# eib-64-large.net
KiCad netlist of a schematic drawn in EAGLE
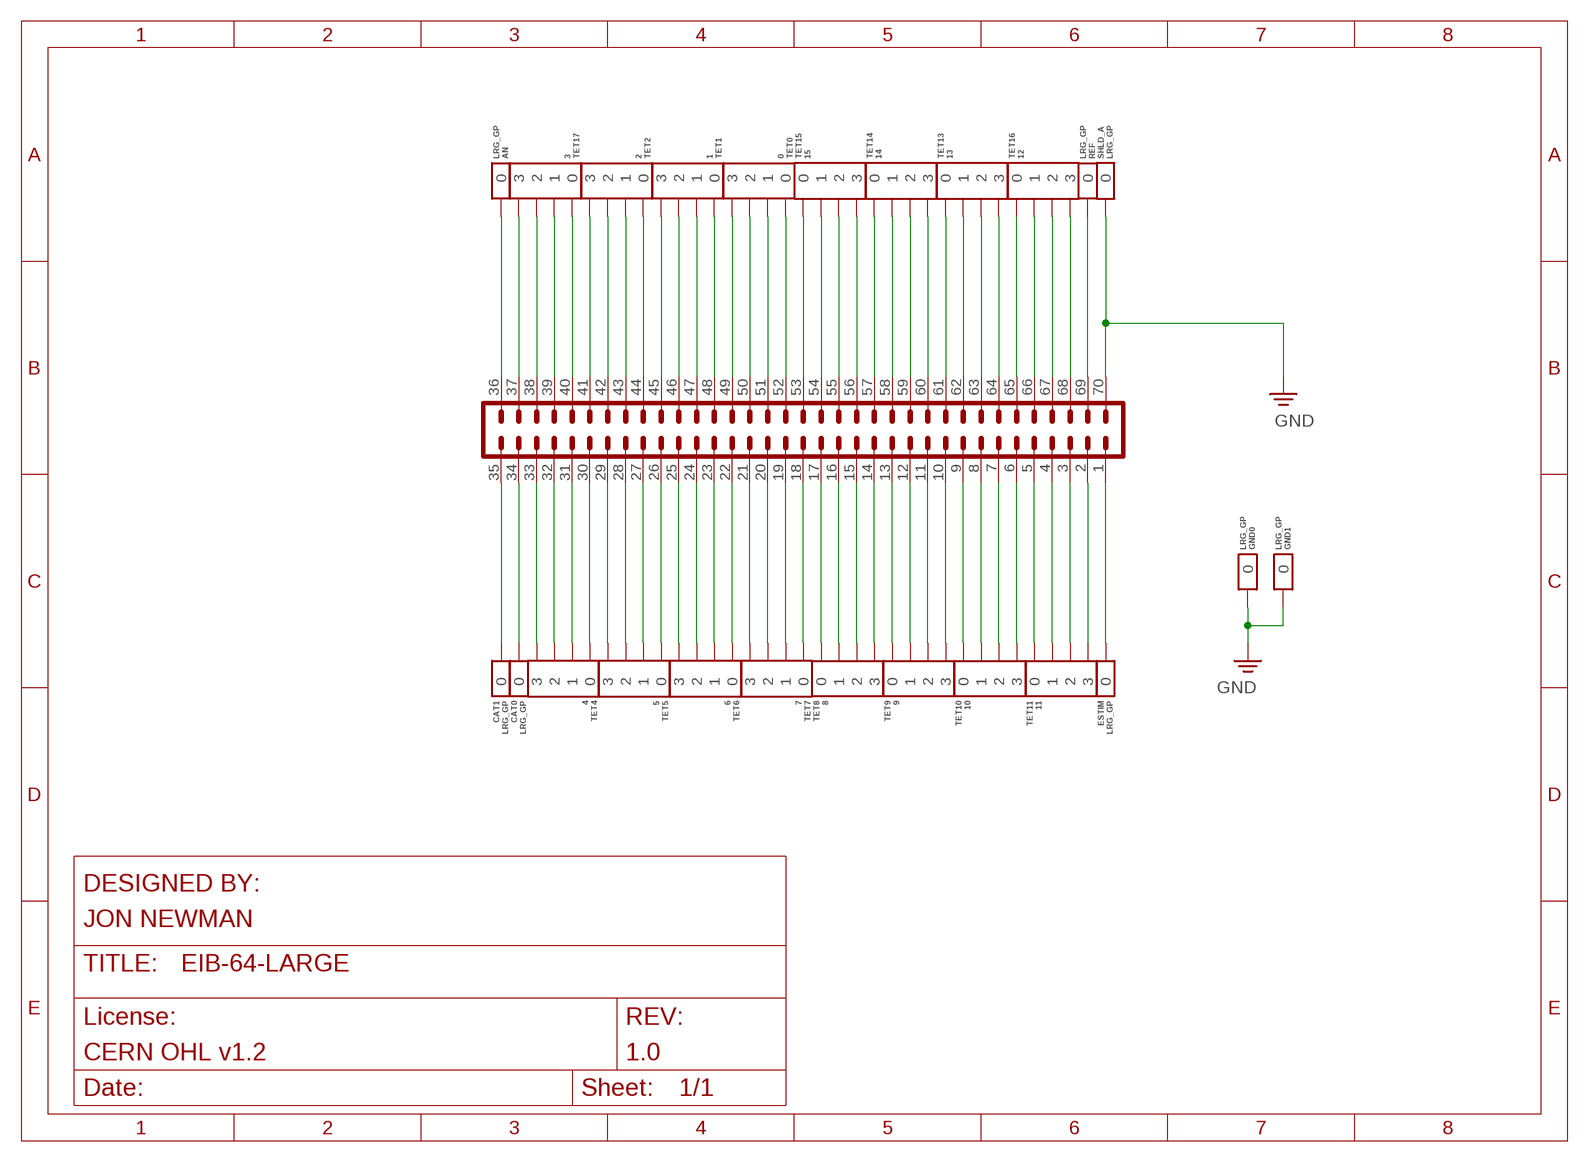
[diagram p0: schematic, sheet 1]

(export (version "E")
  (design (tool "Eeschema 10.0.6"))
  (components
    (comp (ref "AN")
      (value "LRG_GP")
      (footprint "eagle-import:GOLDPIN_0.5ID_0.7OD")
      (libsource (lib "eagle-import") (part "GOLDPIN_0.5ID_0.7OD"))
    )
    (comp (ref "CAT0")
      (value "LRG_GP")
      (footprint "eagle-import:GOLDPIN_0.5ID_0.7OD")
      (libsource (lib "eagle-import") (part "GOLDPIN_0.5ID_0.7OD"))
    )
    (comp (ref "CAT1")
      (value "LRG_GP")
      (footprint "eagle-import:GOLDPIN_0.5ID_0.7OD")
      (libsource (lib "eagle-import") (part "GOLDPIN_0.5ID_0.7OD"))
    )
    (comp (ref "ESTIM")
      (value "LRG_GP")
      (footprint "eagle-import:GOLDPIN_0.5ID_0.7OD")
      (libsource (lib "eagle-import") (part "GOLDPIN_0.5ID_0.7OD"))
    )
    (comp (ref "GND0")
      (value "LRG_GP")
      (footprint "eagle-import:GOLDPIN_0.5ID_0.7OD")
      (libsource (lib "eagle-import") (part "GOLDPIN_0.5ID_0.7OD"))
    )
    (comp (ref "GND1")
      (value "LRG_GP")
      (footprint "eagle-import:GOLDPIN_0.5ID_0.7OD")
      (libsource (lib "eagle-import") (part "GOLDPIN_0.5ID_0.7OD"))
    )
    (comp (ref "J1")
      (value "DF40-REC")
      (footprint "eagle-import:DDF40-70REC-LRG")
      (libsource (lib "eagle-import") (part "PINHD-2X35_DF40REF-LRG"))
    )
    (comp (ref "REF")
      (value "LRG_GP")
      (footprint "eagle-import:GOLDPIN_0.5ID_0.7OD")
      (libsource (lib "eagle-import") (part "GOLDPIN_0.5ID_0.7OD"))
    )
    (comp (ref "SHLD_A")
      (value "LRG_GP")
      (footprint "eagle-import:GOLDPIN_0.5ID_0.7OD")
      (libsource (lib "eagle-import") (part "GOLDPIN_0.5ID_0.7OD"))
    )
    (comp (ref "TET0")
      (value "0")
      (footprint "eagle-import:TETRODE_128_0.5ID_0.7OD")
      (libsource (lib "eagle-import") (part "TETRODE_128_0.5ID_0.7OD"))
    )
    (comp (ref "TET1")
      (value "1")
      (footprint "eagle-import:TETRODE_128_0.5ID_0.7OD")
      (libsource (lib "eagle-import") (part "TETRODE_128_0.5ID_0.7OD"))
    )
    (comp (ref "TET2")
      (value "2")
      (footprint "eagle-import:TETRODE_128_0.5ID_0.7OD")
      (libsource (lib "eagle-import") (part "TETRODE_128_0.5ID_0.7OD"))
    )
    (comp (ref "TET4")
      (value "4")
      (footprint "eagle-import:TETRODE_128_0.5ID_0.7OD")
      (libsource (lib "eagle-import") (part "TETRODE_128_0.5ID_0.7OD"))
    )
    (comp (ref "TET5")
      (value "5")
      (footprint "eagle-import:TETRODE_128_0.5ID_0.7OD")
      (libsource (lib "eagle-import") (part "TETRODE_128_0.5ID_0.7OD"))
    )
    (comp (ref "TET6")
      (value "6")
      (footprint "eagle-import:TETRODE_128_0.5ID_0.7OD")
      (libsource (lib "eagle-import") (part "TETRODE_128_0.5ID_0.7OD"))
    )
    (comp (ref "TET7")
      (value "7")
      (footprint "eagle-import:TETRODE_128_0.5ID_0.7OD")
      (libsource (lib "eagle-import") (part "TETRODE_128_0.5ID_0.7OD"))
    )
    (comp (ref "TET8")
      (value "8")
      (footprint "eagle-import:TETRODE_128_0.5ID_0.7OD")
      (libsource (lib "eagle-import") (part "TETRODE_128_0.5ID_0.7OD"))
    )
    (comp (ref "TET9")
      (value "9")
      (footprint "eagle-import:TETRODE_128_0.5ID_0.7OD")
      (libsource (lib "eagle-import") (part "TETRODE_128_0.5ID_0.7OD"))
    )
    (comp (ref "TET10")
      (value "10")
      (footprint "eagle-import:TETRODE_128_0.5ID_0.7OD")
      (libsource (lib "eagle-import") (part "TETRODE_128_0.5ID_0.7OD"))
    )
    (comp (ref "TET11")
      (value "11")
      (footprint "eagle-import:TETRODE_128_0.5ID_0.7OD")
      (libsource (lib "eagle-import") (part "TETRODE_128_0.5ID_0.7OD"))
    )
    (comp (ref "TET13")
      (value "13")
      (footprint "eagle-import:TETRODE_128_0.5ID_0.7OD")
      (libsource (lib "eagle-import") (part "TETRODE_128_0.5ID_0.7OD"))
    )
    (comp (ref "TET14")
      (value "14")
      (footprint "eagle-import:TETRODE_128_0.5ID_0.7OD")
      (libsource (lib "eagle-import") (part "TETRODE_128_0.5ID_0.7OD"))
    )
    (comp (ref "TET15")
      (value "15")
      (footprint "eagle-import:TETRODE_128_0.5ID_0.7OD")
      (libsource (lib "eagle-import") (part "TETRODE_128_0.5ID_0.7OD"))
    )
    (comp (ref "TET16")
      (value "12")
      (footprint "eagle-import:TETRODE_128_0.5ID_0.7OD")
      (libsource (lib "eagle-import") (part "TETRODE_128_0.5ID_0.7OD"))
    )
    (comp (ref "TET17")
      (value "3")
      (footprint "eagle-import:TETRODE_128_0.5ID_0.7OD")
      (libsource (lib "eagle-import") (part "TETRODE_128_0.5ID_0.7OD"))
    )
  )
  (nets
    (net (code "1") (name "GND") (class "Default")
      (node (ref "GND0") (pin "P$1") (pinfunction "0_P$1") (pintype "bidirectional"))
      (node (ref "GND1") (pin "P$1") (pinfunction "0_P$1") (pintype "bidirectional"))
      (node (ref "J1") (pin "70") (pinfunction "70_70") (pintype "bidirectional"))
      (node (ref "SHLD_A") (pin "P$1") (pinfunction "0_P$1") (pintype "bidirectional"))
    )
    (net (code "2") (name "Net-(AN-0)") (class "Default")
      (node (ref "AN") (pin "P$1") (pinfunction "0_P$1") (pintype "bidirectional"))
      (node (ref "J1") (pin "36") (pinfunction "36_36") (pintype "bidirectional"))
    )
    (net (code "3") (name "Net-(CAT0-0)") (class "Default")
      (node (ref "CAT0") (pin "P$1") (pinfunction "0_P$1") (pintype "bidirectional"))
      (node (ref "J1") (pin "34") (pinfunction "34_34") (pintype "bidirectional"))
    )
    (net (code "4") (name "Net-(CAT1-0)") (class "Default")
      (node (ref "CAT1") (pin "P$1") (pinfunction "0_P$1") (pintype "bidirectional"))
      (node (ref "J1") (pin "35") (pinfunction "35_35") (pintype "bidirectional"))
    )
    (net (code "5") (name "Net-(ESTIM-0)") (class "Default")
      (node (ref "ESTIM") (pin "P$1") (pinfunction "0_P$1") (pintype "bidirectional"))
      (node (ref "J1") (pin "1") (pinfunction "1_1") (pintype "bidirectional"))
    )
    (net (code "6") (name "Net-(J1-Pad2)") (class "Default")
      (node (ref "J1") (pin "2") (pinfunction "2_2") (pintype "bidirectional"))
      (node (ref "TET11") (pin "3") (pinfunction "3_3") (pintype "bidirectional"))
    )
    (net (code "7") (name "Net-(J1-Pad3)") (class "Default")
      (node (ref "J1") (pin "3") (pinfunction "3_3") (pintype "bidirectional"))
      (node (ref "TET11") (pin "2") (pinfunction "2_2") (pintype "bidirectional"))
    )
    (net (code "8") (name "Net-(J1-Pad4)") (class "Default")
      (node (ref "J1") (pin "4") (pinfunction "4_4") (pintype "bidirectional"))
      (node (ref "TET11") (pin "1") (pinfunction "1_1") (pintype "bidirectional"))
    )
    (net (code "9") (name "Net-(J1-Pad5)") (class "Default")
      (node (ref "J1") (pin "5") (pinfunction "5_5") (pintype "bidirectional"))
      (node (ref "TET11") (pin "0") (pinfunction "0_0") (pintype "bidirectional"))
    )
    (net (code "10") (name "Net-(J1-Pad6)") (class "Default")
      (node (ref "J1") (pin "6") (pinfunction "6_6") (pintype "bidirectional"))
      (node (ref "TET10") (pin "3") (pinfunction "3_3") (pintype "bidirectional"))
    )
    (net (code "11") (name "Net-(J1-Pad7)") (class "Default")
      (node (ref "J1") (pin "7") (pinfunction "7_7") (pintype "bidirectional"))
      (node (ref "TET10") (pin "2") (pinfunction "2_2") (pintype "bidirectional"))
    )
    (net (code "12") (name "Net-(J1-Pad8)") (class "Default")
      (node (ref "J1") (pin "8") (pinfunction "8_8") (pintype "bidirectional"))
      (node (ref "TET10") (pin "1") (pinfunction "1_1") (pintype "bidirectional"))
    )
    (net (code "13") (name "Net-(J1-Pad9)") (class "Default")
      (node (ref "J1") (pin "9") (pinfunction "9_9") (pintype "bidirectional"))
      (node (ref "TET10") (pin "0") (pinfunction "0_0") (pintype "bidirectional"))
    )
    (net (code "14") (name "Net-(J1-Pad10)") (class "Default")
      (node (ref "J1") (pin "10") (pinfunction "10_10") (pintype "bidirectional"))
      (node (ref "TET9") (pin "3") (pinfunction "3_3") (pintype "bidirectional"))
    )
    (net (code "15") (name "Net-(J1-Pad11)") (class "Default")
      (node (ref "J1") (pin "11") (pinfunction "11_11") (pintype "bidirectional"))
      (node (ref "TET9") (pin "2") (pinfunction "2_2") (pintype "bidirectional"))
    )
    (net (code "16") (name "Net-(J1-Pad12)") (class "Default")
      (node (ref "J1") (pin "12") (pinfunction "12_12") (pintype "bidirectional"))
      (node (ref "TET9") (pin "1") (pinfunction "1_1") (pintype "bidirectional"))
    )
    (net (code "17") (name "Net-(J1-Pad13)") (class "Default")
      (node (ref "J1") (pin "13") (pinfunction "13_13") (pintype "bidirectional"))
      (node (ref "TET9") (pin "0") (pinfunction "0_0") (pintype "bidirectional"))
    )
    (net (code "18") (name "Net-(J1-Pad14)") (class "Default")
      (node (ref "J1") (pin "14") (pinfunction "14_14") (pintype "bidirectional"))
      (node (ref "TET8") (pin "3") (pinfunction "3_3") (pintype "bidirectional"))
    )
    (net (code "19") (name "Net-(J1-Pad15)") (class "Default")
      (node (ref "J1") (pin "15") (pinfunction "15_15") (pintype "bidirectional"))
      (node (ref "TET8") (pin "2") (pinfunction "2_2") (pintype "bidirectional"))
    )
    (net (code "20") (name "Net-(J1-Pad16)") (class "Default")
      (node (ref "J1") (pin "16") (pinfunction "16_16") (pintype "bidirectional"))
      (node (ref "TET8") (pin "1") (pinfunction "1_1") (pintype "bidirectional"))
    )
    (net (code "21") (name "Net-(J1-Pad17)") (class "Default")
      (node (ref "J1") (pin "17") (pinfunction "17_17") (pintype "bidirectional"))
      (node (ref "TET8") (pin "0") (pinfunction "0_0") (pintype "bidirectional"))
    )
    (net (code "22") (name "Net-(J1-Pad18)") (class "Default")
      (node (ref "J1") (pin "18") (pinfunction "18_18") (pintype "bidirectional"))
      (node (ref "TET7") (pin "0") (pinfunction "0_0") (pintype "bidirectional"))
    )
    (net (code "23") (name "Net-(J1-Pad19)") (class "Default")
      (node (ref "J1") (pin "19") (pinfunction "19_19") (pintype "bidirectional"))
      (node (ref "TET7") (pin "1") (pinfunction "1_1") (pintype "bidirectional"))
    )
    (net (code "24") (name "Net-(J1-Pad20)") (class "Default")
      (node (ref "J1") (pin "20") (pinfunction "20_20") (pintype "bidirectional"))
      (node (ref "TET7") (pin "2") (pinfunction "2_2") (pintype "bidirectional"))
    )
    (net (code "25") (name "Net-(J1-Pad21)") (class "Default")
      (node (ref "J1") (pin "21") (pinfunction "21_21") (pintype "bidirectional"))
      (node (ref "TET7") (pin "3") (pinfunction "3_3") (pintype "bidirectional"))
    )
    (net (code "26") (name "Net-(J1-Pad22)") (class "Default")
      (node (ref "J1") (pin "22") (pinfunction "22_22") (pintype "bidirectional"))
      (node (ref "TET6") (pin "0") (pinfunction "0_0") (pintype "bidirectional"))
    )
    (net (code "27") (name "Net-(J1-Pad23)") (class "Default")
      (node (ref "J1") (pin "23") (pinfunction "23_23") (pintype "bidirectional"))
      (node (ref "TET6") (pin "1") (pinfunction "1_1") (pintype "bidirectional"))
    )
    (net (code "28") (name "Net-(J1-Pad24)") (class "Default")
      (node (ref "J1") (pin "24") (pinfunction "24_24") (pintype "bidirectional"))
      (node (ref "TET6") (pin "2") (pinfunction "2_2") (pintype "bidirectional"))
    )
    (net (code "29") (name "Net-(J1-Pad25)") (class "Default")
      (node (ref "J1") (pin "25") (pinfunction "25_25") (pintype "bidirectional"))
      (node (ref "TET6") (pin "3") (pinfunction "3_3") (pintype "bidirectional"))
    )
    (net (code "30") (name "Net-(J1-Pad26)") (class "Default")
      (node (ref "J1") (pin "26") (pinfunction "26_26") (pintype "bidirectional"))
      (node (ref "TET5") (pin "0") (pinfunction "0_0") (pintype "bidirectional"))
    )
    (net (code "31") (name "Net-(J1-Pad27)") (class "Default")
      (node (ref "J1") (pin "27") (pinfunction "27_27") (pintype "bidirectional"))
      (node (ref "TET5") (pin "1") (pinfunction "1_1") (pintype "bidirectional"))
    )
    (net (code "32") (name "Net-(J1-Pad28)") (class "Default")
      (node (ref "J1") (pin "28") (pinfunction "28_28") (pintype "bidirectional"))
      (node (ref "TET5") (pin "2") (pinfunction "2_2") (pintype "bidirectional"))
    )
    (net (code "33") (name "Net-(J1-Pad29)") (class "Default")
      (node (ref "J1") (pin "29") (pinfunction "29_29") (pintype "bidirectional"))
      (node (ref "TET5") (pin "3") (pinfunction "3_3") (pintype "bidirectional"))
    )
    (net (code "34") (name "Net-(J1-Pad30)") (class "Default")
      (node (ref "J1") (pin "30") (pinfunction "30_30") (pintype "bidirectional"))
      (node (ref "TET4") (pin "0") (pinfunction "0_0") (pintype "bidirectional"))
    )
    (net (code "35") (name "Net-(J1-Pad31)") (class "Default")
      (node (ref "J1") (pin "31") (pinfunction "31_31") (pintype "bidirectional"))
      (node (ref "TET4") (pin "1") (pinfunction "1_1") (pintype "bidirectional"))
    )
    (net (code "36") (name "Net-(J1-Pad32)") (class "Default")
      (node (ref "J1") (pin "32") (pinfunction "32_32") (pintype "bidirectional"))
      (node (ref "TET4") (pin "2") (pinfunction "2_2") (pintype "bidirectional"))
    )
    (net (code "37") (name "Net-(J1-Pad33)") (class "Default")
      (node (ref "J1") (pin "33") (pinfunction "33_33") (pintype "bidirectional"))
      (node (ref "TET4") (pin "3") (pinfunction "3_3") (pintype "bidirectional"))
    )
    (net (code "38") (name "Net-(J1-Pad37)") (class "Default")
      (node (ref "J1") (pin "37") (pinfunction "37_37") (pintype "bidirectional"))
      (node (ref "TET17") (pin "3") (pinfunction "3_3") (pintype "bidirectional"))
    )
    (net (code "39") (name "Net-(J1-Pad38)") (class "Default")
      (node (ref "J1") (pin "38") (pinfunction "38_38") (pintype "bidirectional"))
      (node (ref "TET17") (pin "2") (pinfunction "2_2") (pintype "bidirectional"))
    )
    (net (code "40") (name "Net-(J1-Pad39)") (class "Default")
      (node (ref "J1") (pin "39") (pinfunction "39_39") (pintype "bidirectional"))
      (node (ref "TET17") (pin "1") (pinfunction "1_1") (pintype "bidirectional"))
    )
    (net (code "41") (name "Net-(J1-Pad40)") (class "Default")
      (node (ref "J1") (pin "40") (pinfunction "40_40") (pintype "bidirectional"))
      (node (ref "TET17") (pin "0") (pinfunction "0_0") (pintype "bidirectional"))
    )
    (net (code "42") (name "Net-(J1-Pad41)") (class "Default")
      (node (ref "J1") (pin "41") (pinfunction "41_41") (pintype "bidirectional"))
      (node (ref "TET2") (pin "3") (pinfunction "3_3") (pintype "bidirectional"))
    )
    (net (code "43") (name "Net-(J1-Pad42)") (class "Default")
      (node (ref "J1") (pin "42") (pinfunction "42_42") (pintype "bidirectional"))
      (node (ref "TET2") (pin "2") (pinfunction "2_2") (pintype "bidirectional"))
    )
    (net (code "44") (name "Net-(J1-Pad43)") (class "Default")
      (node (ref "J1") (pin "43") (pinfunction "43_43") (pintype "bidirectional"))
      (node (ref "TET2") (pin "1") (pinfunction "1_1") (pintype "bidirectional"))
    )
    (net (code "45") (name "Net-(J1-Pad44)") (class "Default")
      (node (ref "J1") (pin "44") (pinfunction "44_44") (pintype "bidirectional"))
      (node (ref "TET2") (pin "0") (pinfunction "0_0") (pintype "bidirectional"))
    )
    (net (code "46") (name "Net-(J1-Pad45)") (class "Default")
      (node (ref "J1") (pin "45") (pinfunction "45_45") (pintype "bidirectional"))
      (node (ref "TET1") (pin "3") (pinfunction "3_3") (pintype "bidirectional"))
    )
    (net (code "47") (name "Net-(J1-Pad46)") (class "Default")
      (node (ref "J1") (pin "46") (pinfunction "46_46") (pintype "bidirectional"))
      (node (ref "TET1") (pin "2") (pinfunction "2_2") (pintype "bidirectional"))
    )
    (net (code "48") (name "Net-(J1-Pad47)") (class "Default")
      (node (ref "J1") (pin "47") (pinfunction "47_47") (pintype "bidirectional"))
      (node (ref "TET1") (pin "1") (pinfunction "1_1") (pintype "bidirectional"))
    )
    (net (code "49") (name "Net-(J1-Pad48)") (class "Default")
      (node (ref "J1") (pin "48") (pinfunction "48_48") (pintype "bidirectional"))
      (node (ref "TET1") (pin "0") (pinfunction "0_0") (pintype "bidirectional"))
    )
    (net (code "50") (name "Net-(J1-Pad49)") (class "Default")
      (node (ref "J1") (pin "49") (pinfunction "49_49") (pintype "bidirectional"))
      (node (ref "TET0") (pin "3") (pinfunction "3_3") (pintype "bidirectional"))
    )
    (net (code "51") (name "Net-(J1-Pad50)") (class "Default")
      (node (ref "J1") (pin "50") (pinfunction "50_50") (pintype "bidirectional"))
      (node (ref "TET0") (pin "2") (pinfunction "2_2") (pintype "bidirectional"))
    )
    (net (code "52") (name "Net-(J1-Pad51)") (class "Default")
      (node (ref "J1") (pin "51") (pinfunction "51_51") (pintype "bidirectional"))
      (node (ref "TET0") (pin "1") (pinfunction "1_1") (pintype "bidirectional"))
    )
    (net (code "53") (name "Net-(J1-Pad52)") (class "Default")
      (node (ref "J1") (pin "52") (pinfunction "52_52") (pintype "bidirectional"))
      (node (ref "TET0") (pin "0") (pinfunction "0_0") (pintype "bidirectional"))
    )
    (net (code "54") (name "Net-(J1-Pad53)") (class "Default")
      (node (ref "J1") (pin "53") (pinfunction "53_53") (pintype "bidirectional"))
      (node (ref "TET15") (pin "0") (pinfunction "0_0") (pintype "bidirectional"))
    )
    (net (code "55") (name "Net-(J1-Pad54)") (class "Default")
      (node (ref "J1") (pin "54") (pinfunction "54_54") (pintype "bidirectional"))
      (node (ref "TET15") (pin "1") (pinfunction "1_1") (pintype "bidirectional"))
    )
    (net (code "56") (name "Net-(J1-Pad55)") (class "Default")
      (node (ref "J1") (pin "55") (pinfunction "55_55") (pintype "bidirectional"))
      (node (ref "TET15") (pin "2") (pinfunction "2_2") (pintype "bidirectional"))
    )
    (net (code "57") (name "Net-(J1-Pad56)") (class "Default")
      (node (ref "J1") (pin "56") (pinfunction "56_56") (pintype "bidirectional"))
      (node (ref "TET15") (pin "3") (pinfunction "3_3") (pintype "bidirectional"))
    )
    (net (code "58") (name "Net-(J1-Pad57)") (class "Default")
      (node (ref "J1") (pin "57") (pinfunction "57_57") (pintype "bidirectional"))
      (node (ref "TET14") (pin "0") (pinfunction "0_0") (pintype "bidirectional"))
    )
    (net (code "59") (name "Net-(J1-Pad58)") (class "Default")
      (node (ref "J1") (pin "58") (pinfunction "58_58") (pintype "bidirectional"))
      (node (ref "TET14") (pin "1") (pinfunction "1_1") (pintype "bidirectional"))
    )
    (net (code "60") (name "Net-(J1-Pad59)") (class "Default")
      (node (ref "J1") (pin "59") (pinfunction "59_59") (pintype "bidirectional"))
      (node (ref "TET14") (pin "2") (pinfunction "2_2") (pintype "bidirectional"))
    )
    (net (code "61") (name "Net-(J1-Pad60)") (class "Default")
      (node (ref "J1") (pin "60") (pinfunction "60_60") (pintype "bidirectional"))
      (node (ref "TET14") (pin "3") (pinfunction "3_3") (pintype "bidirectional"))
    )
    (net (code "62") (name "Net-(J1-Pad61)") (class "Default")
      (node (ref "J1") (pin "61") (pinfunction "61_61") (pintype "bidirectional"))
      (node (ref "TET13") (pin "0") (pinfunction "0_0") (pintype "bidirectional"))
    )
    (net (code "63") (name "Net-(J1-Pad62)") (class "Default")
      (node (ref "J1") (pin "62") (pinfunction "62_62") (pintype "bidirectional"))
      (node (ref "TET13") (pin "1") (pinfunction "1_1") (pintype "bidirectional"))
    )
    (net (code "64") (name "Net-(J1-Pad63)") (class "Default")
      (node (ref "J1") (pin "63") (pinfunction "63_63") (pintype "bidirectional"))
      (node (ref "TET13") (pin "2") (pinfunction "2_2") (pintype "bidirectional"))
    )
    (net (code "65") (name "Net-(J1-Pad64)") (class "Default")
      (node (ref "J1") (pin "64") (pinfunction "64_64") (pintype "bidirectional"))
      (node (ref "TET13") (pin "3") (pinfunction "3_3") (pintype "bidirectional"))
    )
    (net (code "66") (name "Net-(J1-Pad65)") (class "Default")
      (node (ref "J1") (pin "65") (pinfunction "65_65") (pintype "bidirectional"))
      (node (ref "TET16") (pin "0") (pinfunction "0_0") (pintype "bidirectional"))
    )
    (net (code "67") (name "Net-(J1-Pad66)") (class "Default")
      (node (ref "J1") (pin "66") (pinfunction "66_66") (pintype "bidirectional"))
      (node (ref "TET16") (pin "1") (pinfunction "1_1") (pintype "bidirectional"))
    )
    (net (code "68") (name "Net-(J1-Pad67)") (class "Default")
      (node (ref "J1") (pin "67") (pinfunction "67_67") (pintype "bidirectional"))
      (node (ref "TET16") (pin "2") (pinfunction "2_2") (pintype "bidirectional"))
    )
    (net (code "69") (name "Net-(J1-Pad68)") (class "Default")
      (node (ref "J1") (pin "68") (pinfunction "68_68") (pintype "bidirectional"))
      (node (ref "TET16") (pin "3") (pinfunction "3_3") (pintype "bidirectional"))
    )
    (net (code "70") (name "Net-(REF-0)") (class "Default")
      (node (ref "J1") (pin "69") (pinfunction "69_69") (pintype "bidirectional"))
      (node (ref "REF") (pin "P$1") (pinfunction "0_P$1") (pintype "bidirectional"))
    )
  )
)
